# untitled.net
KiCad netlist of a schematic drawn in EAGLE
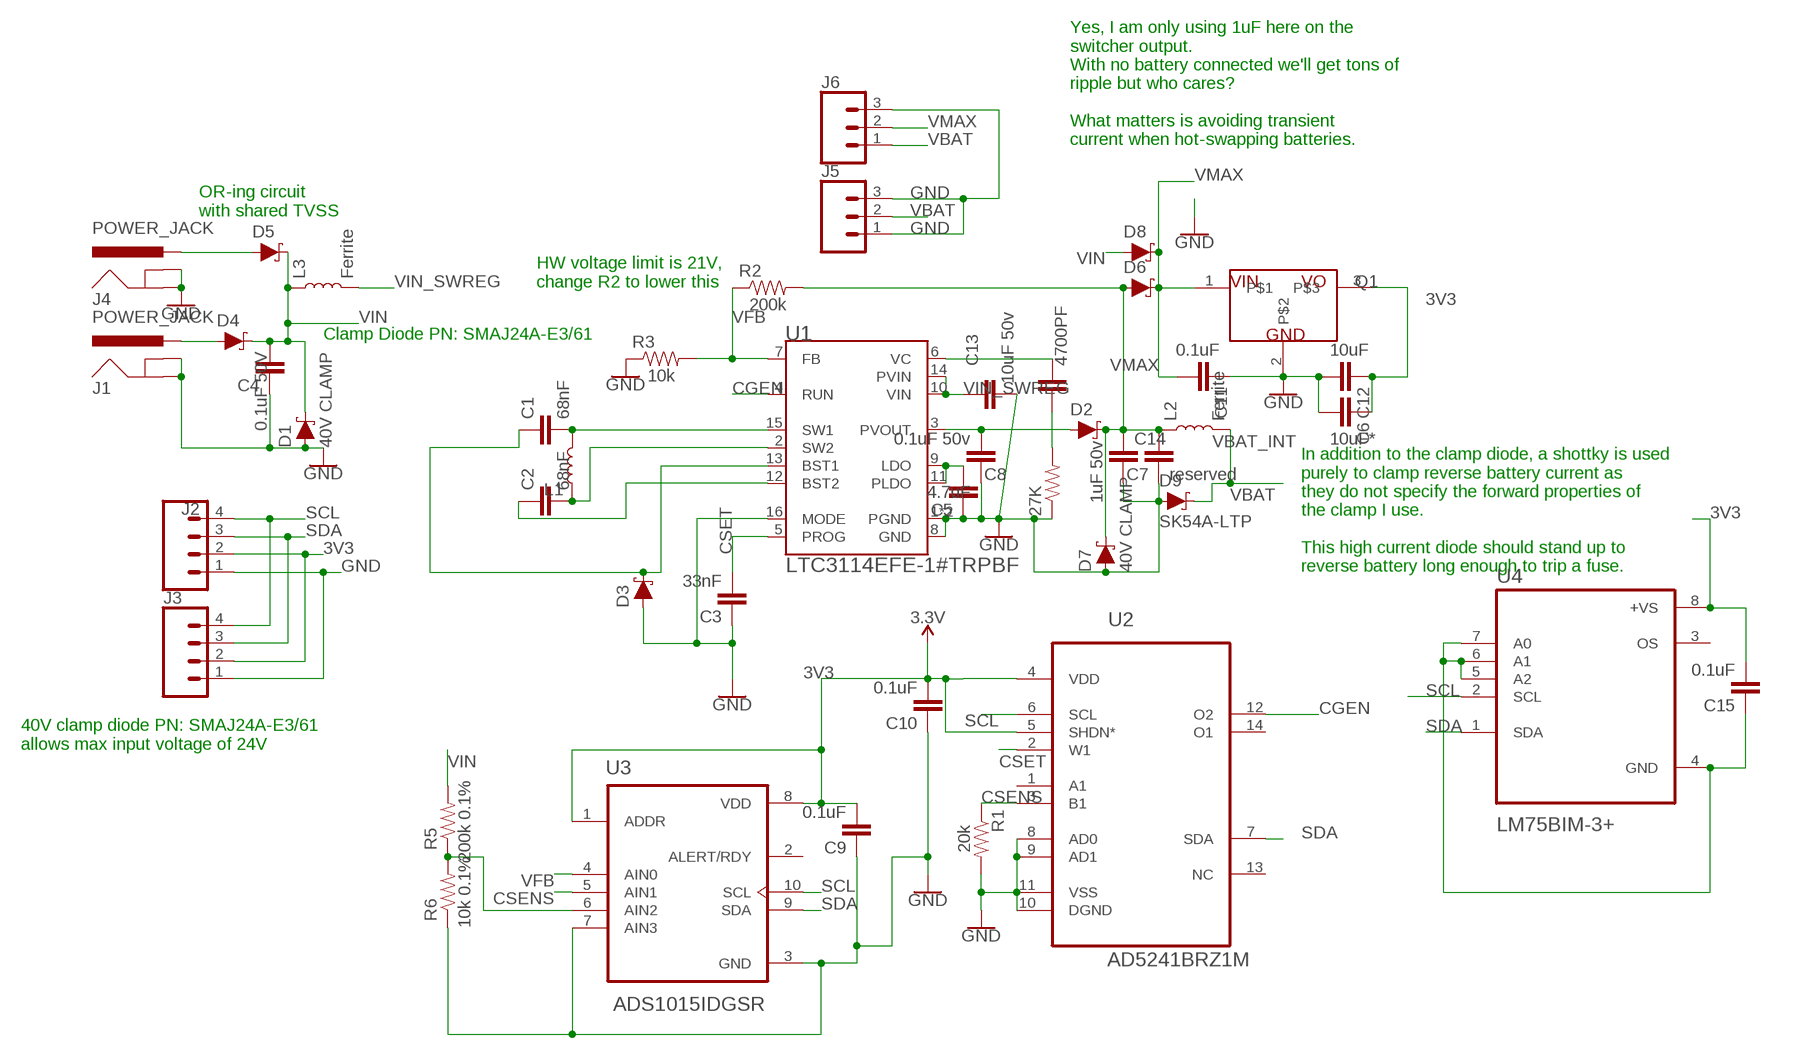
[diagram p0: schematic, sheet 1]

(export (version "E")
  (design (tool "Eeschema 10.0.6"))
  (components
    (comp (ref "27K")
      (value "RESISTOR0805")
      (footprint "eagle-import:0805-EZ")
      (libsource (lib "eagle-import") (part "RESISTOR0805"))
    )
    (comp (ref "4700PF")
      (value "1.0uF")
      (footprint "eagle-import:0805-EZ")
      (libsource (lib "eagle-import") (part "smd_passives_easy_1.0UF-0805-25V-10%"))
    )
    (comp (ref "C1")
      (value "68nF")
      (footprint "eagle-import:0805-EZ")
      (libsource (lib "eagle-import") (part "smd_passives_easy_1.0UF-0805-25V-10%"))
    )
    (comp (ref "C2")
      (value "68nF")
      (footprint "eagle-import:0805-EZ")
      (libsource (lib "eagle-import") (part "smd_passives_easy_1.0UF-0805-25V-10%"))
    )
    (comp (ref "C3")
      (value "33nF")
      (footprint "eagle-import:0805-EZ")
      (libsource (lib "eagle-import") (part "smd_passives_easy_1.0UF-0805-25V-10%"))
    )
    (comp (ref "C4")
      (value "0.1uF 50V")
      (footprint "eagle-import:0805-EZ")
      (libsource (lib "eagle-import") (part "smd_passives_easy_1.0UF-0805-25V-10%"))
    )
    (comp (ref "C5")
      (value "4.7uF")
      (footprint "eagle-import:0805-EZ")
      (libsource (lib "eagle-import") (part "smd_passives_easy_1.0UF-0805-25V-10%"))
    )
    (comp (ref "C6")
      (value "10uF*")
      (footprint "eagle-import:0805-EZ")
      (libsource (lib "eagle-import") (part "smd_passives_easy_1.0UF-0805-25V-10%"))
    )
    (comp (ref "C7")
      (value "reserved")
      (footprint "eagle-import:1206")
      (libsource (lib "eagle-import") (part "1.0UF-1206-50V-10%"))
    )
    (comp (ref "C8")
      (value "0.1uF 50v")
      (footprint "eagle-import:0805-EZ")
      (libsource (lib "eagle-import") (part "smd_passives_easy_1.0UF-0805-25V-10%"))
    )
    (comp (ref "C9")
      (value "0.1uF")
      (footprint "eagle-import:0805-EZ")
      (libsource (lib "eagle-import") (part "smd_passives_easy_1.0UF-0805-25V-10%"))
    )
    (comp (ref "C10")
      (value "0.1uF")
      (footprint "eagle-import:0805-EZ")
      (libsource (lib "eagle-import") (part "smd_passives_easy_1.0UF-0805-25V-10%"))
    )
    (comp (ref "C11")
      (value "0.1uF")
      (footprint "eagle-import:0805-EZ")
      (libsource (lib "eagle-import") (part "smd_passives_easy_1.0UF-0805-25V-10%"))
    )
    (comp (ref "C12")
      (value "10uF")
      (footprint "eagle-import:0805-EZ")
      (libsource (lib "eagle-import") (part "smd_passives_easy_1.0UF-0805-25V-10%"))
    )
    (comp (ref "C13")
      (value "10uF 50v")
      (footprint "eagle-import:1206")
      (libsource (lib "eagle-import") (part "1.0UF-1206-50V-10%"))
    )
    (comp (ref "C14")
      (value "1uF 50v")
      (footprint "eagle-import:0805-EZ")
      (libsource (lib "eagle-import") (part "smd_passives_easy_1.0UF-0805-25V-10%"))
    )
    (comp (ref "C15")
      (value "0.1uF")
      (footprint "eagle-import:0805-EZ")
      (libsource (lib "eagle-import") (part "smd_passives_easy_1.0UF-0805-25V-10%"))
    )
    (comp (ref "D1")
      (value "40V CLAMP")
      (footprint "eagle-import:SMA-DIODE")
      (libsource (lib "eagle-import") (part "DIODE-SCHOTTKY-B340A"))
    )
    (comp (ref "D2")
      (value "3A/40V/500mV")
      (footprint "eagle-import:SMA-DIODE")
      (libsource (lib "eagle-import") (part "DIODE-SCHOTTKY-B340A"))
    )
    (comp (ref "D3")
      (value "3A/40V/500mV")
      (footprint "eagle-import:SMA-DIODE")
      (libsource (lib "eagle-import") (part "DIODE-SCHOTTKY-B340A"))
    )
    (comp (ref "D4")
      (value "3A/40V/500mV")
      (footprint "eagle-import:SMA-DIODE")
      (libsource (lib "eagle-import") (part "DIODE-SCHOTTKY-B340A"))
    )
    (comp (ref "D5")
      (value "3A/40V/500mV")
      (footprint "eagle-import:SMA-DIODE")
      (libsource (lib "eagle-import") (part "DIODE-SCHOTTKY-B340A"))
    )
    (comp (ref "D6")
      (value "3A/40V/500mV")
      (footprint "eagle-import:SMA-DIODE")
      (libsource (lib "eagle-import") (part "DIODE-SCHOTTKY-B340A"))
    )
    (comp (ref "D7")
      (value "40V CLAMP")
      (footprint "eagle-import:SMA-DIODE")
      (libsource (lib "eagle-import") (part "DIODE-SCHOTTKY-B340A"))
    )
    (comp (ref "D8")
      (value "3A/40V/500mV")
      (footprint "eagle-import:SMA-DIODE")
      (libsource (lib "eagle-import") (part "DIODE-SCHOTTKY-B340A"))
    )
    (comp (ref "D9")
      (value "SK54A-LTP")
      (footprint "eagle-import:SMA-DIODE")
      (libsource (lib "eagle-import") (part "DIODE-SCHOTTKY-B340A"))
    )
    (comp (ref "J1")
      (value "POWER_JACK")
      (footprint "eagle-import:POWER_JACK_PTH")
      (libsource (lib "eagle-import") (part "POWER_JACK"))
    )
    (comp (ref "J2")
      (value "CONN_04JST-PTH-VERT")
      (footprint "eagle-import:JST-4-PTH-VERT")
      (libsource (lib "eagle-import") (part "CONN_04JST-PTH-VERT"))
    )
    (comp (ref "J3")
      (value "CONN_04JST-PTH-VERT")
      (footprint "eagle-import:JST-4-PTH-VERT")
      (libsource (lib "eagle-import") (part "CONN_04JST-PTH-VERT"))
    )
    (comp (ref "J4")
      (value "POWER_JACK")
      (footprint "eagle-import:POWER_JACK_PTH")
      (libsource (lib "eagle-import") (part "POWER_JACK"))
    )
    (comp (ref "J5")
      (value "CONN_03SCREW_LOCK")
      (footprint "eagle-import:SCREWTERMINAL-3.5MM-3_LOCK.007S")
      (libsource (lib "eagle-import") (part "CONN_03SCREW_LOCK"))
    )
    (comp (ref "J6")
      (value "CONN_03SCREW_LOCK")
      (footprint "eagle-import:SCREWTERMINAL-3.5MM-3_LOCK.007S")
      (libsource (lib "eagle-import") (part "CONN_03SCREW_LOCK"))
    )
    (comp (ref "L1")
      (value "27µH/±20%/3.3A")
      (footprint "eagle-import:INDUCTOR_SDR1307")
      (libsource (lib "eagle-import") (part "INDUCTOR-SDR13-27UH"))
    )
    (comp (ref "L2")
      (value "Ferrite")
      (footprint "eagle-import:0805")
      (libsource (lib "eagle-import") (part "INDUCTOR-0805-3.3UH"))
    )
    (comp (ref "L3")
      (value "Ferrite")
      (footprint "eagle-import:0805")
      (libsource (lib "eagle-import") (part "INDUCTOR-0805-3.3UH"))
    )
    (comp (ref "Q1")
      (value "BD433M5FP-CE2TO252_STM")
      (footprint "eagle-import:TO252_STM")
      (libsource (lib "eagle-import") (part "BD433M5FP-CE2TO252_STM"))
    )
    (comp (ref "R1")
      (value "20k")
      (footprint "eagle-import:0805-EZ")
      (libsource (lib "eagle-import") (part "RESISTOR0805"))
    )
    (comp (ref "R2")
      (value "200k")
      (footprint "eagle-import:0805-EZ")
      (libsource (lib "eagle-import") (part "RESISTOR0805"))
    )
    (comp (ref "R3")
      (value "10k")
      (footprint "eagle-import:0805-EZ")
      (libsource (lib "eagle-import") (part "RESISTOR0805"))
    )
    (comp (ref "R5")
      (value "200k 0.1%")
      (footprint "eagle-import:0805-EZ")
      (libsource (lib "eagle-import") (part "RESISTOR0805"))
    )
    (comp (ref "R6")
      (value "10k 0.1%")
      (footprint "eagle-import:0805-EZ")
      (libsource (lib "eagle-import") (part "RESISTOR0805"))
    )
    (comp (ref "U1")
      (value "LTC3114EFE-1#TRPBF")
      (footprint "eagle-import:SOP65P640X110-17N")
      (fields (field (name "MF") "Linear Technology/Analog"))
      (libsource (lib "eagle-import") (part "LTC3114EFE-1#TRPBF"))
    )
    (comp (ref "U2")
      (value "AD5241BRZ1M")
      (footprint "eagle-import:SOIC127P600X175-14N")
      (fields (field (name "MF") "Analog Devices"))
      (libsource (lib "eagle-import") (part "AD5241BRZ1M"))
    )
    (comp (ref "U3")
      (value "ADS1015IDGSR")
      (footprint "eagle-import:SOP50P490X110-10N")
      (fields (field (name "MF") "Texas Instruments"))
      (libsource (lib "eagle-import") (part "ADS1015IDGSR"))
    )
    (comp (ref "U4")
      (value "LM75BIM-3+")
      (footprint "eagle-import:SOIC127P600X175-8N")
      (fields (field (name "MF") "Maxim Integrated"))
      (libsource (lib "eagle-import") (part "LM75BIM-3+"))
    )
  )
  (nets
    (net (code "1") (name "/CGEN") (class "Default")
      (node (ref "U1") (pin "4") (pinfunction "RUN_4") (pintype "input"))
      (node (ref "U2") (pin "12") (pinfunction "O2_12") (pintype "passive"))
    )
    (net (code "2") (name "/CSENS") (class "Default")
      (node (ref "R1") (pin "1") (pinfunction "1_1") (pintype "passive"))
      (node (ref "U2") (pin "3") (pinfunction "B1_3") (pintype "passive"))
      (node (ref "U3") (pin "5") (pinfunction "AIN1_5") (pintype "input"))
    )
    (net (code "3") (name "/CSET") (class "Default")
      (node (ref "C3") (pin "2") (pinfunction "2_2") (pintype "passive"))
      (node (ref "U1") (pin "5") (pinfunction "PROG_5") (pintype "output"))
      (node (ref "U2") (pin "2") (pinfunction "W1_2") (pintype "passive"))
    )
    (net (code "4") (name "/SCL") (class "Default")
      (node (ref "J2") (pin "4") (pinfunction "4_4") (pintype "passive"))
      (node (ref "J3") (pin "4") (pinfunction "4_4") (pintype "passive"))
      (node (ref "U2") (pin "6") (pinfunction "SCL_6") (pintype "passive"))
      (node (ref "U3") (pin "10") (pinfunction "SCL_10") (pintype "input"))
      (node (ref "U4") (pin "2") (pinfunction "SCL_2") (pintype "input"))
    )
    (net (code "5") (name "/SDA") (class "Default")
      (node (ref "J2") (pin "3") (pinfunction "3_3") (pintype "passive"))
      (node (ref "J3") (pin "3") (pinfunction "3_3") (pintype "passive"))
      (node (ref "U2") (pin "7") (pinfunction "SDA_7") (pintype "passive"))
      (node (ref "U3") (pin "9") (pinfunction "SDA_9") (pintype "bidirectional"))
      (node (ref "U4") (pin "1") (pinfunction "SDA_1") (pintype "bidirectional"))
    )
    (net (code "6") (name "/VBAT") (class "Default")
      (node (ref "D9") (pin "C") (pinfunction "C_C") (pintype "passive"))
      (node (ref "J5") (pin "2") (pinfunction "2_2") (pintype "passive"))
      (node (ref "J6") (pin "1") (pinfunction "1_1") (pintype "passive"))
      (node (ref "L2") (pin "2") (pinfunction "2_2") (pintype "passive"))
    )
    (net (code "7") (name "/VBAT_INT") (class "Default")
      (node (ref "C14") (pin "1") (pinfunction "1_1") (pintype "passive"))
      (node (ref "C7") (pin "2") (pinfunction "2_2") (pintype "passive"))
      (node (ref "D2") (pin "C") (pinfunction "C_C") (pintype "passive"))
      (node (ref "D6") (pin "A") (pinfunction "A_A") (pintype "passive"))
      (node (ref "D7") (pin "C") (pinfunction "C_C") (pintype "passive"))
      (node (ref "L2") (pin "1") (pinfunction "1_1") (pintype "passive"))
      (node (ref "R2") (pin "2") (pinfunction "2_2") (pintype "passive"))
    )
    (net (code "8") (name "/VFB") (class "Default")
      (node (ref "R2") (pin "1") (pinfunction "1_1") (pintype "passive"))
      (node (ref "R3") (pin "2") (pinfunction "2_2") (pintype "passive"))
      (node (ref "U1") (pin "7") (pinfunction "FB_7") (pintype "input"))
      (node (ref "U3") (pin "4") (pinfunction "AIN0_4") (pintype "input"))
    )
    (net (code "9") (name "/VIN") (class "Default")
      (node (ref "C4") (pin "2") (pinfunction "2_2") (pintype "passive"))
      (node (ref "D1") (pin "C") (pinfunction "C_C") (pintype "passive"))
      (node (ref "D4") (pin "C") (pinfunction "C_C") (pintype "passive"))
      (node (ref "D5") (pin "C") (pinfunction "C_C") (pintype "passive"))
      (node (ref "D8") (pin "A") (pinfunction "A_A") (pintype "passive"))
      (node (ref "L3") (pin "1") (pinfunction "1_1") (pintype "passive"))
      (node (ref "R5") (pin "2") (pinfunction "2_2") (pintype "passive"))
    )
    (net (code "10") (name "/VIN_SWREG") (class "Default")
      (node (ref "C13") (pin "1") (pinfunction "1_1") (pintype "passive"))
      (node (ref "L3") (pin "2") (pinfunction "2_2") (pintype "passive"))
      (node (ref "U1") (pin "10") (pinfunction "VIN_10") (pintype "power_in"))
      (node (ref "U1") (pin "14") (pinfunction "PVIN_14") (pintype "power_in"))
    )
    (net (code "11") (name "/VMAX") (class "Default")
      (node (ref "C11") (pin "2") (pinfunction "2_2") (pintype "passive"))
      (node (ref "D6") (pin "C") (pinfunction "C_C") (pintype "passive"))
      (node (ref "D8") (pin "C") (pinfunction "C_C") (pintype "passive"))
      (node (ref "J6") (pin "2") (pinfunction "2_2") (pintype "passive"))
      (node (ref "Q1") (pin "1") (pinfunction "P$1_1") (pintype "bidirectional"))
    )
    (net (code "12") (name "3.3V") (class "Default")
      (node (ref "C10") (pin "2") (pinfunction "2_2") (pintype "passive"))
      (node (ref "C12") (pin "1") (pinfunction "1_1") (pintype "passive"))
      (node (ref "C15") (pin "2") (pinfunction "2_2") (pintype "passive"))
      (node (ref "C6") (pin "1") (pinfunction "1_1") (pintype "passive"))
      (node (ref "C9") (pin "2") (pinfunction "2_2") (pintype "passive"))
      (node (ref "J2") (pin "2") (pinfunction "2_2") (pintype "passive"))
      (node (ref "J3") (pin "2") (pinfunction "2_2") (pintype "passive"))
      (node (ref "Q1") (pin "3") (pinfunction "P$3_3") (pintype "bidirectional"))
      (node (ref "U2") (pin "4") (pinfunction "VDD_4") (pintype "power_in"))
      (node (ref "U2") (pin "5") (pinfunction "SHDN*_5") (pintype "passive"))
      (node (ref "U3") (pin "1") (pinfunction "ADDR_1") (pintype "input"))
      (node (ref "U3") (pin "8") (pinfunction "VDD_8") (pintype "power_in"))
      (node (ref "U4") (pin "8") (pinfunction "+VS_8") (pintype "power_in"))
    )
    (net (code "13") (name "GND") (class "Default")
      (node (ref "27K") (pin "1") (pinfunction "1_1") (pintype "passive"))
      (node (ref "C10") (pin "1") (pinfunction "1_1") (pintype "passive"))
      (node (ref "C11") (pin "1") (pinfunction "1_1") (pintype "passive"))
      (node (ref "C12") (pin "2") (pinfunction "2_2") (pintype "passive"))
      (node (ref "C13") (pin "2") (pinfunction "2_2") (pintype "passive"))
      (node (ref "C14") (pin "2") (pinfunction "2_2") (pintype "passive"))
      (node (ref "C3") (pin "1") (pinfunction "1_1") (pintype "passive"))
      (node (ref "C4") (pin "1") (pinfunction "1_1") (pintype "passive"))
      (node (ref "C5") (pin "1") (pinfunction "1_1") (pintype "passive"))
      (node (ref "C6") (pin "2") (pinfunction "2_2") (pintype "passive"))
      (node (ref "C7") (pin "1") (pinfunction "1_1") (pintype "passive"))
      (node (ref "C8") (pin "1") (pinfunction "1_1") (pintype "passive"))
      (node (ref "C9") (pin "1") (pinfunction "1_1") (pintype "passive"))
      (node (ref "D1") (pin "A") (pinfunction "A_A") (pintype "passive"))
      (node (ref "D3") (pin "A") (pinfunction "A_A") (pintype "passive"))
      (node (ref "D7") (pin "A") (pinfunction "A_A") (pintype "passive"))
      (node (ref "D9") (pin "A") (pinfunction "A_A") (pintype "passive"))
      (node (ref "J1") (pin "GND") (pinfunction "GND_GND") (pintype "bidirectional"))
      (node (ref "J1") (pin "GNDBREAK") (pinfunction "GNDBREAK_GNDBREAK") (pintype "bidirectional"))
      (node (ref "J2") (pin "1") (pinfunction "1_1") (pintype "passive"))
      (node (ref "J3") (pin "1") (pinfunction "1_1") (pintype "passive"))
      (node (ref "J4") (pin "GND") (pinfunction "GND_GND") (pintype "bidirectional"))
      (node (ref "J4") (pin "GNDBREAK") (pinfunction "GNDBREAK_GNDBREAK") (pintype "bidirectional"))
      (node (ref "J5") (pin "1") (pinfunction "1_1") (pintype "passive"))
      (node (ref "J5") (pin "3") (pinfunction "3_3") (pintype "passive"))
      (node (ref "J6") (pin "3") (pinfunction "3_3") (pintype "passive"))
      (node (ref "Q1") (pin "2") (pinfunction "P$2_2") (pintype "bidirectional"))
      (node (ref "R1") (pin "2") (pinfunction "2_2") (pintype "passive"))
      (node (ref "R3") (pin "1") (pinfunction "1_1") (pintype "passive"))
      (node (ref "R6") (pin "1") (pinfunction "1_1") (pintype "passive"))
      (node (ref "U1") (pin "1") (pinfunction "PGND_1") (pintype "power_in"))
      (node (ref "U1") (pin "16") (pinfunction "MODE_16") (pintype "input"))
      (node (ref "U1") (pin "17") (pinfunction "PGND_17") (pintype "power_in"))
      (node (ref "U1") (pin "8") (pinfunction "GND_8") (pintype "power_in"))
      (node (ref "U2") (pin "10") (pinfunction "DGND_10") (pintype "passive"))
      (node (ref "U2") (pin "11") (pinfunction "VSS_11") (pintype "power_in"))
      (node (ref "U2") (pin "8") (pinfunction "AD0_8") (pintype "passive"))
      (node (ref "U2") (pin "9") (pinfunction "AD1_9") (pintype "passive"))
      (node (ref "U3") (pin "3") (pinfunction "GND_3") (pintype "power_in"))
      (node (ref "U3") (pin "7") (pinfunction "AIN3_7") (pintype "input"))
    )
    (net (code "14") (name "Net-(27K-Pad2)") (class "Default")
      (node (ref "27K") (pin "2") (pinfunction "2_2") (pintype "passive"))
      (node (ref "4700PF") (pin "1") (pinfunction "1_1") (pintype "passive"))
    )
    (net (code "15") (name "Net-(D4-PadA)") (class "Default")
      (node (ref "D4") (pin "A") (pinfunction "A_A") (pintype "passive"))
      (node (ref "J1") (pin "PWR") (pinfunction "PWR_PWR") (pintype "bidirectional"))
    )
    (net (code "16") (name "Net-(D5-PadA)") (class "Default")
      (node (ref "D5") (pin "A") (pinfunction "A_A") (pintype "passive"))
      (node (ref "J4") (pin "PWR") (pinfunction "PWR_PWR") (pintype "bidirectional"))
    )
    (net (code "17") (name "Net-(L1-1)") (class "Default")
      (node (ref "C2") (pin "2") (pinfunction "2_2") (pintype "passive"))
      (node (ref "L1") (pin "P$1") (pinfunction "1_P$1") (pintype "passive"))
      (node (ref "U1") (pin "2") (pinfunction "SW2_2") (pintype "passive"))
    )
    (net (code "18") (name "Net-(L1-2)") (class "Default")
      (node (ref "C1") (pin "2") (pinfunction "2_2") (pintype "passive"))
      (node (ref "L1") (pin "P$2") (pinfunction "2_P$2") (pintype "passive"))
      (node (ref "U1") (pin "15") (pinfunction "SW1_15") (pintype "passive"))
    )
    (net (code "19") (name "Net-(U1-BST1)") (class "Default")
      (node (ref "C1") (pin "1") (pinfunction "1_1") (pintype "passive"))
      (node (ref "D3") (pin "C") (pinfunction "C_C") (pintype "passive"))
      (node (ref "U1") (pin "13") (pinfunction "BST1_13") (pintype "input"))
    )
    (net (code "20") (name "Net-(U1-BST2)") (class "Default")
      (node (ref "C2") (pin "1") (pinfunction "1_1") (pintype "passive"))
      (node (ref "U1") (pin "12") (pinfunction "BST2_12") (pintype "input"))
    )
    (net (code "21") (name "Net-(U1-LDO)") (class "Default")
      (node (ref "C5") (pin "2") (pinfunction "2_2") (pintype "passive"))
      (node (ref "U1") (pin "11") (pinfunction "PLDO_11") (pintype "output"))
      (node (ref "U1") (pin "9") (pinfunction "LDO_9") (pintype "output"))
    )
    (net (code "22") (name "Net-(U1-PVOUT)") (class "Default")
      (node (ref "C8") (pin "2") (pinfunction "2_2") (pintype "passive"))
      (node (ref "D2") (pin "A") (pinfunction "A_A") (pintype "passive"))
      (node (ref "U1") (pin "3") (pinfunction "PVOUT_3") (pintype "output"))
    )
    (net (code "23") (name "Net-(U1-VC)") (class "Default")
      (node (ref "4700PF") (pin "2") (pinfunction "2_2") (pintype "passive"))
      (node (ref "U1") (pin "6") (pinfunction "VC_6") (pintype "power_in"))
    )
    (net (code "24") (name "Net-(U3-AIN2)") (class "Default")
      (node (ref "R5") (pin "1") (pinfunction "1_1") (pintype "passive"))
      (node (ref "R6") (pin "2") (pinfunction "2_2") (pintype "passive"))
      (node (ref "U3") (pin "6") (pinfunction "AIN2_6") (pintype "input"))
    )
    (net (code "25") (name "Net-(U4-A0)") (class "Default")
      (node (ref "C15") (pin "1") (pinfunction "1_1") (pintype "passive"))
      (node (ref "U4") (pin "4") (pinfunction "GND_4") (pintype "power_in"))
      (node (ref "U4") (pin "5") (pinfunction "A2_5") (pintype "input"))
      (node (ref "U4") (pin "6") (pinfunction "A1_6") (pintype "input"))
      (node (ref "U4") (pin "7") (pinfunction "A0_7") (pintype "input"))
    )
    (net (code "26") (name "unconnected-(U2-A1-Pad1)") (class "Default")
      (node (ref "U2") (pin "1") (pinfunction "A1_1") (pintype "passive"))
    )
    (net (code "27") (name "unconnected-(U2-NC-Pad13)") (class "Default")
      (node (ref "U2") (pin "13") (pinfunction "NC_13") (pintype "passive"))
    )
    (net (code "28") (name "unconnected-(U2-O1-Pad14)") (class "Default")
      (node (ref "U2") (pin "14") (pinfunction "O1_14") (pintype "passive"))
    )
    (net (code "29") (name "unconnected-(U3-ALERT{slash}RDY-Pad2)") (class "Default")
      (node (ref "U3") (pin "2") (pinfunction "ALERT/RDY_2") (pintype "output"))
    )
    (net (code "30") (name "unconnected-(U4-OS-Pad3)") (class "Default")
      (node (ref "U4") (pin "3") (pinfunction "OS_3") (pintype "output"))
    )
  )
)
